# EFAPS.net
KiCad netlist of a schematic drawn in EAGLE
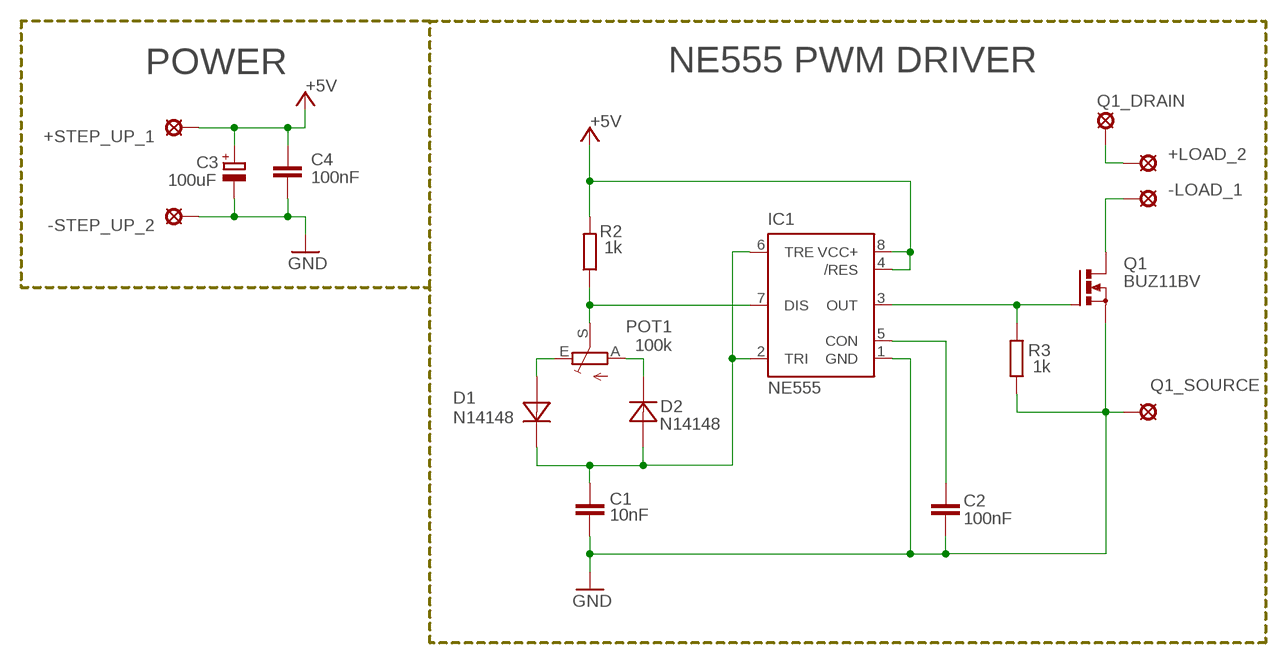
[diagram p0: schematic, sheet 1]

(export (version "E")
  (design (tool "Eeschema 10.0.6"))
  (components
    (comp (ref "+LOAD_2")
      (value "SE14")
      (footprint "eagle-import:SE14")
      (libsource (lib "eagle-import") (part "SE14"))
    )
    (comp (ref "+STEP_UP_1")
      (value "SE14")
      (footprint "eagle-import:SE14")
      (libsource (lib "eagle-import") (part "SE14"))
    )
    (comp (ref "-LOAD_1")
      (value "SE14")
      (footprint "eagle-import:SE14")
      (libsource (lib "eagle-import") (part "SE14"))
    )
    (comp (ref "-STEP_UP_2")
      (value "SE14")
      (footprint "eagle-import:SE14")
      (libsource (lib "eagle-import") (part "SE14"))
    )
    (comp (ref "C1")
      (value "10nF")
      (footprint "eagle-import:C50-45-75")
      (libsource (lib "eagle-import") (part "C-EU050-045-075"))
    )
    (comp (ref "C2")
      (value "100nF")
      (footprint "eagle-import:C50-45-75")
      (libsource (lib "eagle-import") (part "C-EU050-045-075"))
    )
    (comp (ref "C3")
      (value "100uF")
      (footprint "eagle-import:C5-8,5")
      (libsource (lib "eagle-import") (part "C-EU-POL'''"))
    )
    (comp (ref "C4")
      (value "100nF")
      (footprint "eagle-import:C50-45-75")
      (libsource (lib "eagle-import") (part "C-EU050-045-075"))
    )
    (comp (ref "D1")
      (value "N14148")
      (footprint "eagle-import:DO35-7")
      (libsource (lib "eagle-import") (part "N14148"))
    )
    (comp (ref "D2")
      (value "N14148")
      (footprint "eagle-import:DO35-7")
      (libsource (lib "eagle-import") (part "N14148"))
    )
    (comp (ref "IC1")
      (value "NE555")
      (footprint "eagle-import:DIL-08")
      (fields (field (name "MF") "Arrow Electronics") (field (name "MPN") "NE555N"))
      (libsource (lib "eagle-import") (part "NE555"))
    )
    (comp (ref "POT1")
      (value "100k")
      (footprint "eagle-import:CA6V")
      (libsource (lib "eagle-import") (part "TRIM_EU-CA6V"))
    )
    (comp (ref "Q1")
      (value "BUZ11BV")
      (footprint "eagle-import:TO220BV")
      (libsource (lib "eagle-import") (part "BUZ11BV"))
    )
    (comp (ref "Q1_DRAIN")
      (value "SE14")
      (footprint "eagle-import:SE14")
      (libsource (lib "eagle-import") (part "SE14"))
    )
    (comp (ref "Q1_SOURCE")
      (value "SE14")
      (footprint "eagle-import:SE14")
      (libsource (lib "eagle-import") (part "SE14"))
    )
    (comp (ref "R2")
      (value "1k")
      (footprint "eagle-import:204_7")
      (libsource (lib "eagle-import") (part "R-EU7"))
    )
    (comp (ref "R3")
      (value "1k")
      (footprint "eagle-import:204_7")
      (libsource (lib "eagle-import") (part "R-EU7"))
    )
  )
  (nets
    (net (code "1") (name "+5V") (class "Default")
      (node (ref "+STEP_UP_1") (pin "MP") (pinfunction "MP_MP") (pintype "passive"))
      (node (ref "C3") (pin "+") (pinfunction "+_+") (pintype "passive"))
      (node (ref "C4") (pin "P$1") (pinfunction "1_P$1") (pintype "passive"))
      (node (ref "IC1") (pin "4") (pinfunction "/RES_4") (pintype "input"))
      (node (ref "IC1") (pin "8") (pinfunction "VCC+_8") (pintype "power_in"))
      (node (ref "R2") (pin "P$2") (pinfunction "2_P$2") (pintype "passive"))
    )
    (net (code "2") (name "GND") (class "Default")
      (node (ref "-STEP_UP_2") (pin "MP") (pinfunction "MP_MP") (pintype "passive"))
      (node (ref "C1") (pin "P$2") (pinfunction "2_P$2") (pintype "passive"))
      (node (ref "C2") (pin "P$2") (pinfunction "2_P$2") (pintype "passive"))
      (node (ref "C3") (pin "-") (pinfunction "-_-") (pintype "passive"))
      (node (ref "C4") (pin "P$2") (pinfunction "2_P$2") (pintype "passive"))
      (node (ref "IC1") (pin "1") (pinfunction "GND_1") (pintype "power_in"))
      (node (ref "Q1") (pin "S") (pinfunction "S_S") (pintype "passive"))
      (node (ref "Q1_SOURCE") (pin "MP") (pinfunction "MP_MP") (pintype "passive"))
      (node (ref "R3") (pin "P$1") (pinfunction "1_P$1") (pintype "passive"))
    )
    (net (code "3") (name "Net-(+LOAD_2-PadMP)") (class "Default")
      (node (ref "+LOAD_2") (pin "MP") (pinfunction "MP_MP") (pintype "passive"))
      (node (ref "Q1_DRAIN") (pin "MP") (pinfunction "MP_MP") (pintype "passive"))
    )
    (net (code "4") (name "Net-(-LOAD_1-PadMP)") (class "Default")
      (node (ref "-LOAD_1") (pin "MP") (pinfunction "MP_MP") (pintype "passive"))
      (node (ref "Q1") (pin "D") (pinfunction "D_D") (pintype "passive"))
    )
    (net (code "5") (name "Net-(C1-1)") (class "Default")
      (node (ref "C1") (pin "P$1") (pinfunction "1_P$1") (pintype "passive"))
      (node (ref "D1") (pin "-") (pinfunction "-_-") (pintype "bidirectional"))
      (node (ref "D2") (pin "+") (pinfunction "+_+") (pintype "bidirectional"))
      (node (ref "IC1") (pin "2") (pinfunction "TRI_2") (pintype "input"))
      (node (ref "IC1") (pin "6") (pinfunction "TRE_6") (pintype "input"))
    )
    (net (code "6") (name "Net-(C2-1)") (class "Default")
      (node (ref "C2") (pin "P$1") (pinfunction "1_P$1") (pintype "passive"))
      (node (ref "IC1") (pin "5") (pinfunction "CON_5") (pintype "input"))
    )
    (net (code "7") (name "Net-(D1-Pad+)") (class "Default")
      (node (ref "D1") (pin "+") (pinfunction "+_+") (pintype "bidirectional"))
      (node (ref "POT1") (pin "E") (pinfunction "E_E") (pintype "passive"))
    )
    (net (code "8") (name "Net-(D2-Pad-)") (class "Default")
      (node (ref "D2") (pin "-") (pinfunction "-_-") (pintype "bidirectional"))
      (node (ref "POT1") (pin "A") (pinfunction "A_A") (pintype "passive"))
    )
    (net (code "9") (name "Net-(IC1-DIS)") (class "Default")
      (node (ref "IC1") (pin "7") (pinfunction "DIS_7") (pintype "input"))
      (node (ref "POT1") (pin "S") (pinfunction "S_S") (pintype "passive"))
      (node (ref "R2") (pin "P$1") (pinfunction "1_P$1") (pintype "passive"))
    )
    (net (code "10") (name "Net-(IC1-OUT)") (class "Default")
      (node (ref "IC1") (pin "3") (pinfunction "OUT_3") (pintype "output"))
      (node (ref "Q1") (pin "G") (pinfunction "G_G") (pintype "passive"))
      (node (ref "R3") (pin "P$2") (pinfunction "2_P$2") (pintype "passive"))
    )
  )
)
